# controleEsp32.net
KiCad netlist of a schematic drawn in Altium Designer
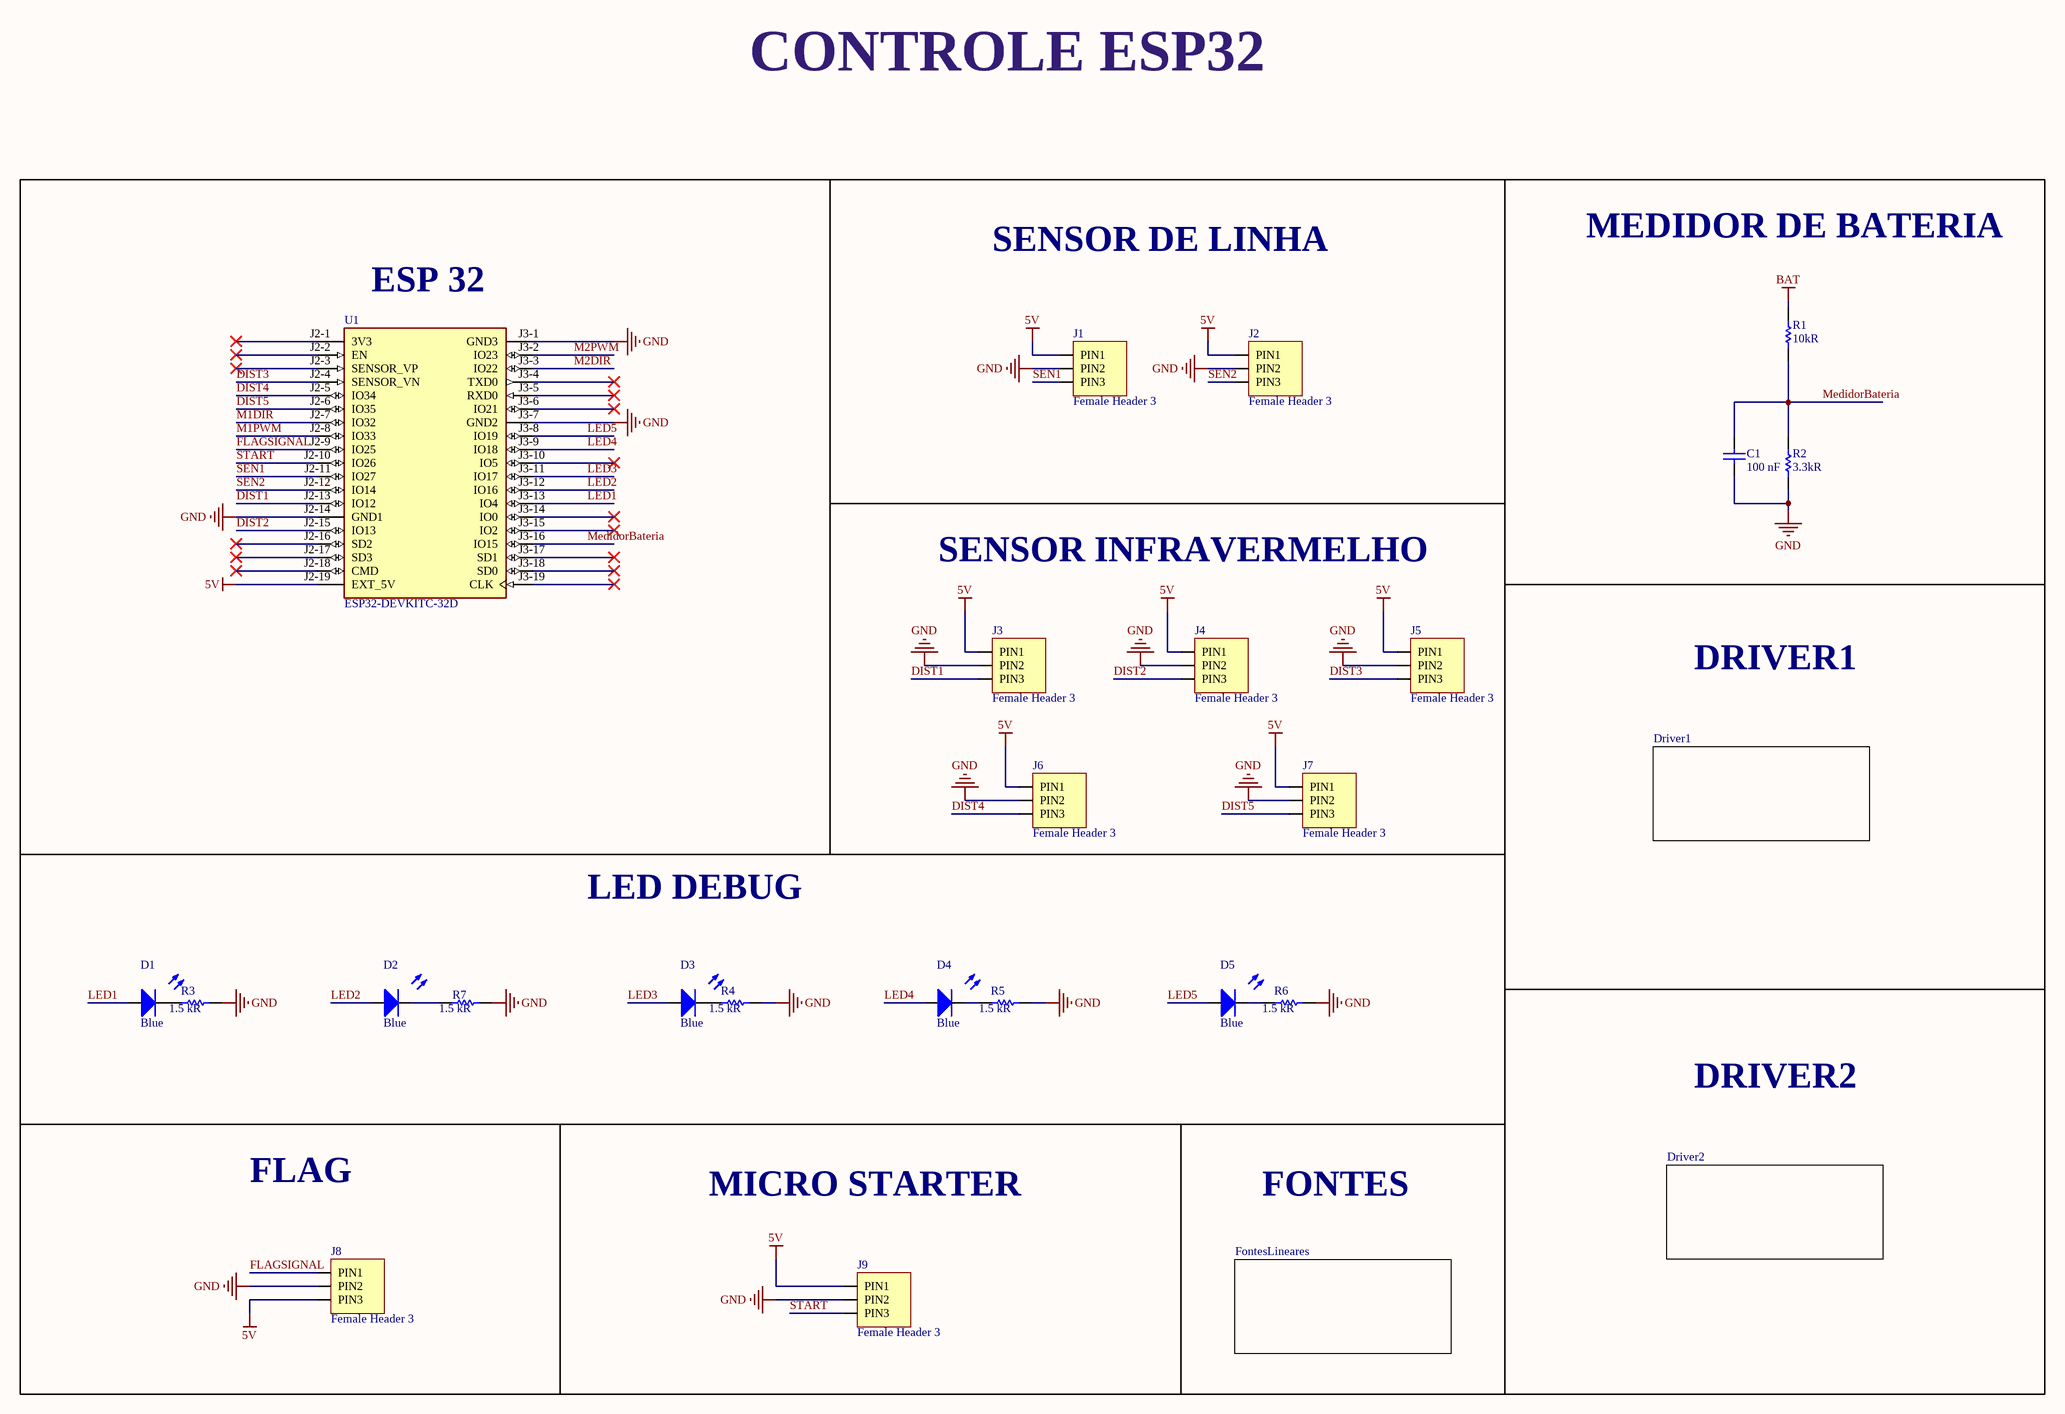
[diagram p0: controleEsp32.SchDoc]

(export (version "E")
  (design (tool "Eeschema 10.0.6"))
  (components
    (comp (ref "C1")
      (value "100 nF")
      (footprint "C0805")
      (description "CAP CER 100 nF 100V X7R 0805")
      (fields (field (name "MANUFACTURER") "Wurth Elektronik") (field (name "PART NUMBER") "885012207128"))
      (libsource (lib "Uai!Tecas") (part "885012207128"))
    )
    (comp (ref "D1")
      (value "Blue")
      (footprint "DIODO_2-SMD-3215")
      (description "LED 75mW BLUE 45MCD 3215")
      (fields
        (field (name "MANUFACTURER") "Everlight Electronics")
        (field (name "PART NUMBER") "EAST3215BA5")
        (field (name "LIBRARY CONTROL - PERSON THAT CHECKED FOOTPRINT") "Lucas")
        (field (name "LIBRARY CONTROL - PERSON THAT CHECKED SCHEMATIC") "Lucas")
        (field (name "LIBRARY CONTROL - PERSON THAT DID THE LAST UPDATE FOOTPRINT") "Stéfany (Ster)")
        (field (name "LIBRARY CONTROL - PERSON THAT DID THE LAST UPDATE SCHEMATIC") "Stéfany (Ster)")
      )
      (libsource (lib "Diodo") (part "EAST3215BA5"))
    )
    (comp (ref "D2")
      (value "Blue")
      (footprint "DIODO_2-SMD-3215")
      (description "LED 75mW BLUE 45MCD 3215")
      (fields
        (field (name "MANUFACTURER") "Everlight Electronics")
        (field (name "PART NUMBER") "EAST3215BA5")
        (field (name "LIBRARY CONTROL - PERSON THAT CHECKED FOOTPRINT") "Lucas")
        (field (name "LIBRARY CONTROL - PERSON THAT CHECKED SCHEMATIC") "Lucas")
        (field (name "LIBRARY CONTROL - PERSON THAT DID THE LAST UPDATE FOOTPRINT") "Stéfany (Ster)")
        (field (name "LIBRARY CONTROL - PERSON THAT DID THE LAST UPDATE SCHEMATIC") "Stéfany (Ster)")
      )
      (libsource (lib "Diodo") (part "EAST3215BA5"))
    )
    (comp (ref "D3")
      (value "Blue")
      (footprint "DIODO_2-SMD-3215")
      (description "LED 75mW BLUE 45MCD 3215")
      (fields
        (field (name "MANUFACTURER") "Everlight Electronics")
        (field (name "PART NUMBER") "EAST3215BA5")
        (field (name "LIBRARY CONTROL - PERSON THAT CHECKED FOOTPRINT") "Lucas")
        (field (name "LIBRARY CONTROL - PERSON THAT CHECKED SCHEMATIC") "Lucas")
        (field (name "LIBRARY CONTROL - PERSON THAT DID THE LAST UPDATE FOOTPRINT") "Stéfany (Ster)")
        (field (name "LIBRARY CONTROL - PERSON THAT DID THE LAST UPDATE SCHEMATIC") "Stéfany (Ster)")
      )
      (libsource (lib "Diodo") (part "EAST3215BA5"))
    )
    (comp (ref "D4")
      (value "Blue")
      (footprint "DIODO_2-SMD-3215")
      (description "LED 75mW BLUE 45MCD 3215")
      (fields
        (field (name "MANUFACTURER") "Everlight Electronics")
        (field (name "PART NUMBER") "EAST3215BA5")
        (field (name "LIBRARY CONTROL - PERSON THAT CHECKED FOOTPRINT") "Lucas")
        (field (name "LIBRARY CONTROL - PERSON THAT CHECKED SCHEMATIC") "Lucas")
        (field (name "LIBRARY CONTROL - PERSON THAT DID THE LAST UPDATE FOOTPRINT") "Stéfany (Ster)")
        (field (name "LIBRARY CONTROL - PERSON THAT DID THE LAST UPDATE SCHEMATIC") "Stéfany (Ster)")
      )
      (libsource (lib "Diodo") (part "EAST3215BA5"))
    )
    (comp (ref "D5")
      (value "Blue")
      (footprint "DIODO_2-SMD-3215")
      (description "LED 75mW BLUE 45MCD 3215")
      (fields
        (field (name "MANUFACTURER") "Everlight Electronics")
        (field (name "PART NUMBER") "EAST3215BA5")
        (field (name "LIBRARY CONTROL - PERSON THAT CHECKED FOOTPRINT") "Lucas")
        (field (name "LIBRARY CONTROL - PERSON THAT CHECKED SCHEMATIC") "Lucas")
        (field (name "LIBRARY CONTROL - PERSON THAT DID THE LAST UPDATE FOOTPRINT") "Stéfany (Ster)")
        (field (name "LIBRARY CONTROL - PERSON THAT DID THE LAST UPDATE SCHEMATIC") "Stéfany (Ster)")
      )
      (libsource (lib "Diodo") (part "EAST3215BA5"))
    )
    (comp (ref "J1")
      (value "Female Header 3")
      (footprint "FEMALE HEADER 3")
      (libsource (lib "Uai!Tecas") (part "Female Header 3"))
    )
    (comp (ref "J2")
      (value "Female Header 3")
      (footprint "FEMALE HEADER 3")
      (libsource (lib "Uai!Tecas") (part "Female Header 3"))
    )
    (comp (ref "J3")
      (value "Female Header 3")
      (footprint "FEMALE HEADER 3")
      (libsource (lib "Uai!Tecas") (part "Female Header 3"))
    )
    (comp (ref "J4")
      (value "Female Header 3")
      (footprint "FEMALE HEADER 3")
      (libsource (lib "Uai!Tecas") (part "Female Header 3"))
    )
    (comp (ref "J5")
      (value "Female Header 3")
      (footprint "FEMALE HEADER 3")
      (libsource (lib "Uai!Tecas") (part "Female Header 3"))
    )
    (comp (ref "J6")
      (value "Female Header 3")
      (footprint "FEMALE HEADER 3")
      (libsource (lib "Uai!Tecas") (part "Female Header 3"))
    )
    (comp (ref "J7")
      (value "Female Header 3")
      (footprint "FEMALE HEADER 3")
      (libsource (lib "Uai!Tecas") (part "Female Header 3"))
    )
    (comp (ref "J8")
      (value "Female Header 3")
      (footprint "FEMALE HEADER 3")
      (libsource (lib "Uai!Tecas") (part "Female Header 3"))
    )
    (comp (ref "J9")
      (value "Female Header 3")
      (footprint "FEMALE HEADER 3")
      (libsource (lib "Uai!Tecas") (part "Female Header 3"))
    )
    (comp (ref "R1")
      (value "10kR")
      (footprint "RESISTOR_0603")
      (description "RES SMD 10K OHM 5% 1/10W 0603")
      (fields
        (field (name "MANUFACTURER") "Yageo")
        (field (name "PART NUMBER") "RC0603JR-0710KL")
        (field (name "LIBRARY CONTROL - PERSON THAT CHECKED SCHEMATIC") "Marcos")
        (field (name "LIBRARY CONTROL - PERSON THAT DID THE LAST UPDATE FOOTPRINT") "Dalarme")
        (field (name "LIBRARY CONTROL - PERSON THAT DID THE LAST UPDATE SCHEMATIC") "Marcos")
      )
      (libsource (lib "Uai!Tecas") (part "RC0603JR-0710KL"))
    )
    (comp (ref "R2")
      (value "3.3kR")
      (footprint "RESISTOR_0603")
      (description "RES SMD 3.3K OHM 1% 1/10W 0603")
      (fields
        (field (name "MANUFACTURER") "TE Connectivity / Holsworthy")
        (field (name "PART NUMBER") "CRGCQ0603F3K3")
        (field (name "LIBRARY CONTROL - PERSON THAT CHECKED FOOTPRINT") "Nikaum")
        (field (name "LIBRARY CONTROL - PERSON THAT CHECKED SCHEMATIC") "Guilherme")
        (field (name "LIBRARY CONTROL - PERSON THAT DID THE LAST UPDATE FOOTPRINT") "Dalarme")
        (field (name "LIBRARY CONTROL - PERSON THAT DID THE LAST UPDATE SCHEMATIC") "Dalarme")
      )
      (libsource (lib "Uai!Tecas") (part "CRGCQ0603F3K3"))
    )
    (comp (ref "R3")
      (value "1.5 kR")
      (footprint "RESISTOR_0805")
      (description "RES SMD 1.5K OHM 1% 1/8W 0805")
      (fields
        (field (name "MANUFACTURER") "Vishay / Dale")
        (field (name "PART NUMBER") "CRCW08051K50FKEAC")
        (field (name "LIBRARY CONTROL - PERSON THAT CHECKED FOOTPRINT") "Nikaum")
        (field (name "LIBRARY CONTROL - PERSON THAT CHECKED SCHEMATIC") "Nikaum")
        (field (name "LIBRARY CONTROL - PERSON THAT DID THE LAST UPDATE FOOTPRINT") "Nicolas")
        (field (name "LIBRARY CONTROL - PERSON THAT DID THE LAST UPDATE SCHEMATIC") "Nikaum")
      )
      (libsource (lib "Uai!Tecas") (part "CRCW08051K50FKEAC"))
    )
    (comp (ref "R4")
      (value "1.5 kR")
      (footprint "RESISTOR_0805")
      (description "RES SMD 1.5K OHM 1% 1/8W 0805")
      (fields
        (field (name "MANUFACTURER") "Vishay / Dale")
        (field (name "PART NUMBER") "CRCW08051K50FKEAC")
        (field (name "LIBRARY CONTROL - PERSON THAT CHECKED FOOTPRINT") "Nikaum")
        (field (name "LIBRARY CONTROL - PERSON THAT CHECKED SCHEMATIC") "Nikaum")
        (field (name "LIBRARY CONTROL - PERSON THAT DID THE LAST UPDATE FOOTPRINT") "Nicolas")
        (field (name "LIBRARY CONTROL - PERSON THAT DID THE LAST UPDATE SCHEMATIC") "Nikaum")
      )
      (libsource (lib "Uai!Tecas") (part "CRCW08051K50FKEAC"))
    )
    (comp (ref "R5")
      (value "1.5 kR")
      (footprint "RESISTOR_0805")
      (description "RES SMD 1.5K OHM 1% 1/8W 0805")
      (fields
        (field (name "MANUFACTURER") "Vishay / Dale")
        (field (name "PART NUMBER") "CRCW08051K50FKEAC")
        (field (name "LIBRARY CONTROL - PERSON THAT CHECKED FOOTPRINT") "Nikaum")
        (field (name "LIBRARY CONTROL - PERSON THAT CHECKED SCHEMATIC") "Nikaum")
        (field (name "LIBRARY CONTROL - PERSON THAT DID THE LAST UPDATE FOOTPRINT") "Nicolas")
        (field (name "LIBRARY CONTROL - PERSON THAT DID THE LAST UPDATE SCHEMATIC") "Nikaum")
      )
      (libsource (lib "Uai!Tecas") (part "CRCW08051K50FKEAC"))
    )
    (comp (ref "R6")
      (value "1.5 kR")
      (footprint "RESISTOR_0805")
      (description "RES SMD 1.5K OHM 1% 1/8W 0805")
      (fields
        (field (name "MANUFACTURER") "Vishay / Dale")
        (field (name "PART NUMBER") "CRCW08051K50FKEAC")
        (field (name "LIBRARY CONTROL - PERSON THAT CHECKED FOOTPRINT") "Nikaum")
        (field (name "LIBRARY CONTROL - PERSON THAT CHECKED SCHEMATIC") "Nikaum")
        (field (name "LIBRARY CONTROL - PERSON THAT DID THE LAST UPDATE FOOTPRINT") "Nicolas")
        (field (name "LIBRARY CONTROL - PERSON THAT DID THE LAST UPDATE SCHEMATIC") "Nikaum")
      )
      (libsource (lib "Uai!Tecas") (part "CRCW08051K50FKEAC"))
    )
    (comp (ref "R7")
      (value "1.5 kR")
      (footprint "RESISTOR_0805")
      (description "RES SMD 1.5K OHM 1% 1/8W 0805")
      (fields
        (field (name "MANUFACTURER") "Vishay / Dale")
        (field (name "PART NUMBER") "CRCW08051K50FKEAC")
        (field (name "LIBRARY CONTROL - PERSON THAT CHECKED FOOTPRINT") "Nikaum")
        (field (name "LIBRARY CONTROL - PERSON THAT CHECKED SCHEMATIC") "Nikaum")
        (field (name "LIBRARY CONTROL - PERSON THAT DID THE LAST UPDATE FOOTPRINT") "Nicolas")
        (field (name "LIBRARY CONTROL - PERSON THAT DID THE LAST UPDATE SCHEMATIC") "Nikaum")
      )
      (libsource (lib "Uai!Tecas") (part "CRCW08051K50FKEAC"))
    )
    (comp (ref "U1")
      (value "ESP32-DEVKITC-32D")
      (footprint "MODULE_ESP32-DEVKITC-32D")
      (description "WiFi Development Tools (802.11) ESP32 General Development Kit, ESP32-WROOM-32D on the board")
      (fields (field (name "MF") "Espressif Systems"))
      (libsource (lib "Uai!Rrior") (part "ESP32-DEVKITC-32D"))
    )
  )
  (nets
    (net (code "1") (name "/DIST1") (class "Default")
      (node (ref "J3") (pin "PIN3") (pinfunction "PIN3_PIN3") (pintype "passive"))
      (node (ref "U1") (pin "J2-13") (pinfunction "IO12_J2-13") (pintype "bidirectional"))
    )
    (net (code "2") (name "/DIST2") (class "Default")
      (node (ref "J4") (pin "PIN3") (pinfunction "PIN3_PIN3") (pintype "passive"))
      (node (ref "U1") (pin "J2-15") (pinfunction "IO13_J2-15") (pintype "bidirectional"))
    )
    (net (code "3") (name "/DIST3") (class "Default")
      (node (ref "J5") (pin "PIN3") (pinfunction "PIN3_PIN3") (pintype "passive"))
      (node (ref "U1") (pin "J2-4") (pinfunction "SENSOR_VN_J2-4") (pintype "input"))
    )
    (net (code "4") (name "/DIST4") (class "Default")
      (node (ref "J6") (pin "PIN3") (pinfunction "PIN3_PIN3") (pintype "passive"))
      (node (ref "U1") (pin "J2-5") (pinfunction "IO34_J2-5") (pintype "bidirectional"))
    )
    (net (code "5") (name "/DIST5") (class "Default")
      (node (ref "J7") (pin "PIN3") (pinfunction "PIN3_PIN3") (pintype "passive"))
      (node (ref "U1") (pin "J2-6") (pinfunction "IO35_J2-6") (pintype "bidirectional"))
    )
    (net (code "6") (name "/FLAGSIGNAL") (class "Default")
      (node (ref "J8") (pin "PIN1") (pinfunction "PIN1_PIN1") (pintype "passive"))
      (node (ref "U1") (pin "J2-9") (pinfunction "IO25_J2-9") (pintype "bidirectional"))
    )
    (net (code "7") (name "/LED1") (class "Default")
      (node (ref "D1") (pin "A") (pinfunction "A_A") (pintype "passive"))
      (node (ref "U1") (pin "J3-13") (pinfunction "IO4_J3-13") (pintype "bidirectional"))
    )
    (net (code "8") (name "/LED2") (class "Default")
      (node (ref "D2") (pin "A") (pinfunction "A_A") (pintype "passive"))
      (node (ref "U1") (pin "J3-12") (pinfunction "IO16_J3-12") (pintype "bidirectional"))
    )
    (net (code "9") (name "/LED3") (class "Default")
      (node (ref "D3") (pin "A") (pinfunction "A_A") (pintype "passive"))
      (node (ref "U1") (pin "J3-11") (pinfunction "IO17_J3-11") (pintype "bidirectional"))
    )
    (net (code "10") (name "/LED4") (class "Default")
      (node (ref "D4") (pin "A") (pinfunction "A_A") (pintype "passive"))
      (node (ref "U1") (pin "J3-9") (pinfunction "IO18_J3-9") (pintype "bidirectional"))
    )
    (net (code "11") (name "/LED5") (class "Default")
      (node (ref "D5") (pin "A") (pinfunction "A_A") (pintype "passive"))
      (node (ref "U1") (pin "J3-8") (pinfunction "IO19_J3-8") (pintype "bidirectional"))
    )
    (net (code "12") (name "/M1DIR") (class "Default")
      (node (ref "U1") (pin "J2-7") (pinfunction "IO32_J2-7") (pintype "bidirectional"))
    )
    (net (code "13") (name "/M1PWM") (class "Default")
      (node (ref "U1") (pin "J2-8") (pinfunction "IO33_J2-8") (pintype "bidirectional"))
    )
    (net (code "14") (name "/M2DIR") (class "Default")
      (node (ref "U1") (pin "J3-3") (pinfunction "IO22_J3-3") (pintype "bidirectional"))
    )
    (net (code "15") (name "/M2PWM") (class "Default")
      (node (ref "U1") (pin "J3-2") (pinfunction "IO23_J3-2") (pintype "bidirectional"))
    )
    (net (code "16") (name "/MedidorBateria") (class "Default")
      (node (ref "C1") (pin "2") (pinfunction "2_2") (pintype "passive"))
      (node (ref "R1") (pin "1") (pinfunction "1_1") (pintype "passive"))
      (node (ref "R2") (pin "2") (pinfunction "2_2") (pintype "passive"))
      (node (ref "U1") (pin "J3-16") (pinfunction "IO15_J3-16") (pintype "bidirectional"))
    )
    (net (code "17") (name "/SEN1") (class "Default")
      (node (ref "J1") (pin "PIN3") (pinfunction "PIN3_PIN3") (pintype "passive"))
      (node (ref "U1") (pin "J2-11") (pinfunction "IO27_J2-11") (pintype "bidirectional"))
    )
    (net (code "18") (name "/SEN2") (class "Default")
      (node (ref "J2") (pin "PIN3") (pinfunction "PIN3_PIN3") (pintype "passive"))
      (node (ref "U1") (pin "J2-12") (pinfunction "IO14_J2-12") (pintype "bidirectional"))
    )
    (net (code "19") (name "/START") (class "Default")
      (node (ref "J9") (pin "PIN3") (pinfunction "PIN3_PIN3") (pintype "passive"))
      (node (ref "U1") (pin "J2-10") (pinfunction "IO26_J2-10") (pintype "bidirectional"))
    )
    (net (code "20") (name "5V") (class "Default")
      (node (ref "J1") (pin "PIN1") (pinfunction "PIN1_PIN1") (pintype "passive"))
      (node (ref "J2") (pin "PIN1") (pinfunction "PIN1_PIN1") (pintype "passive"))
      (node (ref "J3") (pin "PIN1") (pinfunction "PIN1_PIN1") (pintype "passive"))
      (node (ref "J4") (pin "PIN1") (pinfunction "PIN1_PIN1") (pintype "passive"))
      (node (ref "J5") (pin "PIN1") (pinfunction "PIN1_PIN1") (pintype "passive"))
      (node (ref "J6") (pin "PIN1") (pinfunction "PIN1_PIN1") (pintype "passive"))
      (node (ref "J7") (pin "PIN1") (pinfunction "PIN1_PIN1") (pintype "passive"))
      (node (ref "J8") (pin "PIN3") (pinfunction "PIN3_PIN3") (pintype "passive"))
      (node (ref "J9") (pin "PIN1") (pinfunction "PIN1_PIN1") (pintype "passive"))
      (node (ref "U1") (pin "J2-19") (pinfunction "EXT_5V_J2-19") (pintype "power_in"))
    )
    (net (code "21") (name "BAT") (class "Default")
      (node (ref "R1") (pin "2") (pinfunction "2_2") (pintype "passive"))
    )
    (net (code "22") (name "GND") (class "Default")
      (node (ref "C1") (pin "1") (pinfunction "1_1") (pintype "passive"))
      (node (ref "J1") (pin "PIN2") (pinfunction "PIN2_PIN2") (pintype "passive"))
      (node (ref "J2") (pin "PIN2") (pinfunction "PIN2_PIN2") (pintype "passive"))
      (node (ref "J3") (pin "PIN2") (pinfunction "PIN2_PIN2") (pintype "passive"))
      (node (ref "J4") (pin "PIN2") (pinfunction "PIN2_PIN2") (pintype "passive"))
      (node (ref "J5") (pin "PIN2") (pinfunction "PIN2_PIN2") (pintype "passive"))
      (node (ref "J6") (pin "PIN2") (pinfunction "PIN2_PIN2") (pintype "passive"))
      (node (ref "J7") (pin "PIN2") (pinfunction "PIN2_PIN2") (pintype "passive"))
      (node (ref "J8") (pin "PIN2") (pinfunction "PIN2_PIN2") (pintype "passive"))
      (node (ref "J9") (pin "PIN2") (pinfunction "PIN2_PIN2") (pintype "passive"))
      (node (ref "R2") (pin "1") (pinfunction "1_1") (pintype "passive"))
      (node (ref "R3") (pin "2") (pinfunction "2_2") (pintype "passive"))
      (node (ref "R4") (pin "2") (pinfunction "2_2") (pintype "passive"))
      (node (ref "R5") (pin "2") (pinfunction "2_2") (pintype "passive"))
      (node (ref "R6") (pin "2") (pinfunction "2_2") (pintype "passive"))
      (node (ref "R7") (pin "2") (pinfunction "2_2") (pintype "passive"))
      (node (ref "U1") (pin "J2-14") (pinfunction "GND1_J2-14") (pintype "power_in"))
      (node (ref "U1") (pin "J3-1") (pinfunction "GND3_J3-1") (pintype "power_in"))
      (node (ref "U1") (pin "J3-7") (pinfunction "GND2_J3-7") (pintype "power_in"))
    )
    (net (code "23") (name "Net-(D1-PadC)") (class "Default")
      (node (ref "D1") (pin "C") (pinfunction "C_C") (pintype "passive"))
      (node (ref "R3") (pin "1") (pinfunction "1_1") (pintype "passive"))
    )
    (net (code "24") (name "Net-(D2-PadC)") (class "Default")
      (node (ref "D2") (pin "C") (pinfunction "C_C") (pintype "passive"))
      (node (ref "R7") (pin "1") (pinfunction "1_1") (pintype "passive"))
    )
    (net (code "25") (name "Net-(D3-PadC)") (class "Default")
      (node (ref "D3") (pin "C") (pinfunction "C_C") (pintype "passive"))
      (node (ref "R4") (pin "1") (pinfunction "1_1") (pintype "passive"))
    )
    (net (code "26") (name "Net-(D4-PadC)") (class "Default")
      (node (ref "D4") (pin "C") (pinfunction "C_C") (pintype "passive"))
      (node (ref "R5") (pin "1") (pinfunction "1_1") (pintype "passive"))
    )
    (net (code "27") (name "Net-(D5-PadC)") (class "Default")
      (node (ref "D5") (pin "C") (pinfunction "C_C") (pintype "passive"))
      (node (ref "R6") (pin "1") (pinfunction "1_1") (pintype "passive"))
    )
    (net (code "28") (name "unconnected-(U1-3V3-PadJ2-1)") (class "Default")
      (node (ref "U1") (pin "J2-1") (pinfunction "3V3_J2-1") (pintype "power_in+no_connect"))
    )
    (net (code "29") (name "unconnected-(U1-CLK-PadJ3-19)") (class "Default")
      (node (ref "U1") (pin "J3-19") (pinfunction "CLK_J3-19") (pintype "input+no_connect"))
    )
    (net (code "30") (name "unconnected-(U1-CMD-PadJ2-18)") (class "Default")
      (node (ref "U1") (pin "J2-18") (pinfunction "CMD_J2-18") (pintype "bidirectional+no_connect"))
    )
    (net (code "31") (name "unconnected-(U1-EN-PadJ2-2)") (class "Default")
      (node (ref "U1") (pin "J2-2") (pinfunction "EN_J2-2") (pintype "input+no_connect"))
    )
    (net (code "32") (name "unconnected-(U1-IO0-PadJ3-14)") (class "Default")
      (node (ref "U1") (pin "J3-14") (pinfunction "IO0_J3-14") (pintype "bidirectional+no_connect"))
    )
    (net (code "33") (name "unconnected-(U1-IO2-PadJ3-15)") (class "Default")
      (node (ref "U1") (pin "J3-15") (pinfunction "IO2_J3-15") (pintype "bidirectional+no_connect"))
    )
    (net (code "34") (name "unconnected-(U1-IO5-PadJ3-10)") (class "Default")
      (node (ref "U1") (pin "J3-10") (pinfunction "IO5_J3-10") (pintype "bidirectional+no_connect"))
    )
    (net (code "35") (name "unconnected-(U1-IO21-PadJ3-6)") (class "Default")
      (node (ref "U1") (pin "J3-6") (pinfunction "IO21_J3-6") (pintype "bidirectional+no_connect"))
    )
    (net (code "36") (name "unconnected-(U1-RXD0-PadJ3-5)") (class "Default")
      (node (ref "U1") (pin "J3-5") (pinfunction "RXD0_J3-5") (pintype "input+no_connect"))
    )
    (net (code "37") (name "unconnected-(U1-SD0-PadJ3-18)") (class "Default")
      (node (ref "U1") (pin "J3-18") (pinfunction "SD0_J3-18") (pintype "bidirectional+no_connect"))
    )
    (net (code "38") (name "unconnected-(U1-SD1-PadJ3-17)") (class "Default")
      (node (ref "U1") (pin "J3-17") (pinfunction "SD1_J3-17") (pintype "bidirectional+no_connect"))
    )
    (net (code "39") (name "unconnected-(U1-SD2-PadJ2-16)") (class "Default")
      (node (ref "U1") (pin "J2-16") (pinfunction "SD2_J2-16") (pintype "bidirectional+no_connect"))
    )
    (net (code "40") (name "unconnected-(U1-SD3-PadJ2-17)") (class "Default")
      (node (ref "U1") (pin "J2-17") (pinfunction "SD3_J2-17") (pintype "bidirectional+no_connect"))
    )
    (net (code "41") (name "unconnected-(U1-SENSOR_VP-PadJ2-3)") (class "Default")
      (node (ref "U1") (pin "J2-3") (pinfunction "SENSOR_VP_J2-3") (pintype "input+no_connect"))
    )
    (net (code "42") (name "unconnected-(U1-TXD0-PadJ3-4)") (class "Default")
      (node (ref "U1") (pin "J3-4") (pinfunction "TXD0_J3-4") (pintype "output+no_connect"))
    )
  )
)
